# MBusTransmitter.net
KiCad netlist of a schematic drawn in EAGLE
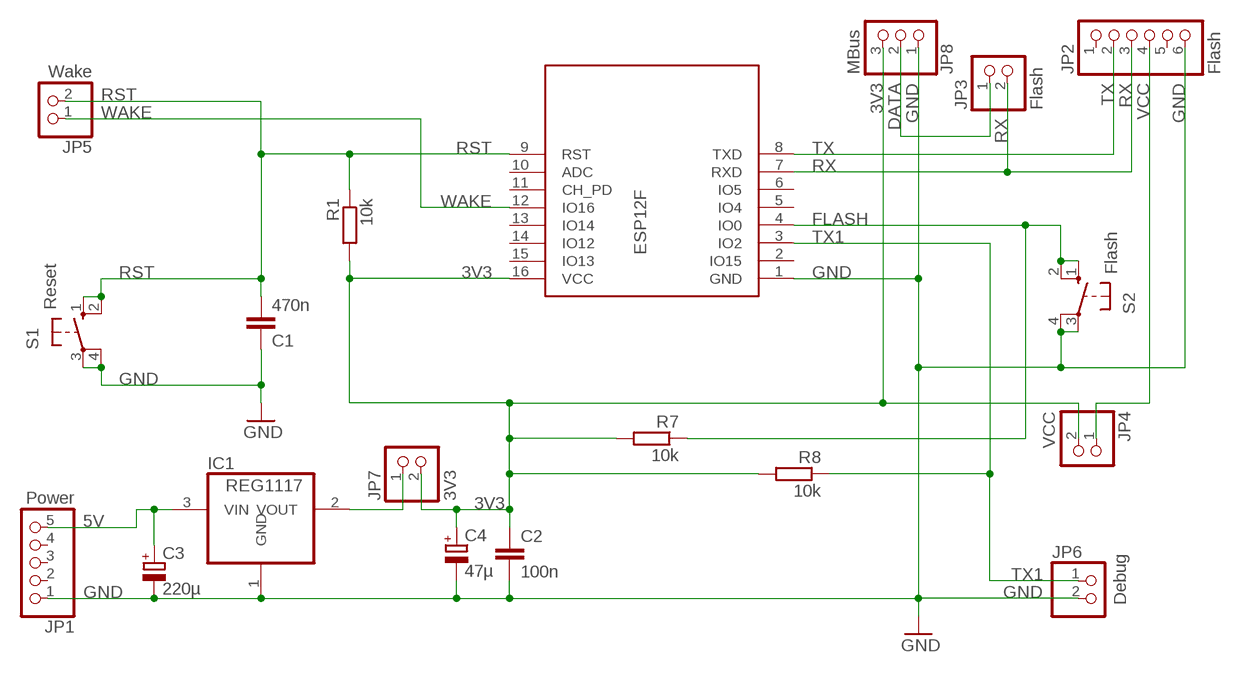
[diagram p0: schematic, sheet 1]

(export (version "E")
  (design (tool "Eeschema 10.0.6"))
  (components
    (comp (ref "C1")
      (value "470n")
      (footprint "eagle-import:C050-024X044")
      (libsource (lib "eagle-import") (part "C-EU050-024X044"))
    )
    (comp (ref "C2")
      (value "100n")
      (footprint "eagle-import:C050-024X044")
      (libsource (lib "eagle-import") (part "C-EU050-024X044"))
    )
    (comp (ref "C3")
      (value "220µ")
      (footprint "eagle-import:E5-10,5")
      (libsource (lib "eagle-import") (part "CPOL-EUE5-10.5"))
    )
    (comp (ref "C4")
      (value "47µ")
      (footprint "eagle-import:E2,5-5")
      (libsource (lib "eagle-import") (part "CPOL-EUE2.5-5"))
    )
    (comp (ref "IC1")
      (value "REG1117")
      (footprint "eagle-import:SOT223")
      (libsource (lib "eagle-import") (part "REG1117"))
    )
    (comp (ref "JP1")
      (value "Power")
      (footprint "eagle-import:1X05")
      (libsource (lib "eagle-import") (part "PINHD-1X5"))
    )
    (comp (ref "JP2")
      (value "Flash")
      (footprint "eagle-import:1X06")
      (libsource (lib "eagle-import") (part "PINHD-1X6"))
    )
    (comp (ref "JP3")
      (value "Flash")
      (footprint "eagle-import:1X02")
      (libsource (lib "eagle-import") (part "PINHD-1X2"))
    )
    (comp (ref "JP4")
      (value "VCC")
      (footprint "eagle-import:1X02")
      (libsource (lib "eagle-import") (part "PINHD-1X2"))
    )
    (comp (ref "JP5")
      (value "Wake")
      (footprint "eagle-import:1X02")
      (libsource (lib "eagle-import") (part "PINHD-1X2"))
    )
    (comp (ref "JP6")
      (value "Debug")
      (footprint "eagle-import:1X02")
      (libsource (lib "eagle-import") (part "PINHD-1X2"))
    )
    (comp (ref "JP7")
      (value "3V3")
      (footprint "eagle-import:1X02")
      (libsource (lib "eagle-import") (part "PINHD-1X2"))
    )
    (comp (ref "JP8")
      (value "MBus")
      (footprint "eagle-import:1X03_90")
      (libsource (lib "eagle-import") (part "PINHD-1X3/90"))
    )
    (comp (ref "R1")
      (value "10k")
      (footprint "eagle-import:0207_10")
      (libsource (lib "eagle-import") (part "R-EU_0207/10"))
    )
    (comp (ref "R7")
      (value "10k")
      (footprint "eagle-import:0207_10")
      (libsource (lib "eagle-import") (part "R-EU_0207/10"))
    )
    (comp (ref "R8")
      (value "10k")
      (footprint "eagle-import:0207_10")
      (libsource (lib "eagle-import") (part "R-EU_0207/10"))
    )
    (comp (ref "S1")
      (value "Reset")
      (footprint "eagle-import:B3F-10XX")
      (fields (field (name "MPN") "B3F-1000"))
      (libsource (lib "eagle-import") (part "10-XX"))
    )
    (comp (ref "S2")
      (value "Flash")
      (footprint "eagle-import:B3F-10XX")
      (fields (field (name "MPN") "B3F-1000"))
      (libsource (lib "eagle-import") (part "10-XX"))
    )
    (comp (ref "U$2")
      (value "ESP12F")
      (footprint "eagle-import:ESP12F")
      (libsource (lib "eagle-import") (part "ESP12F"))
    )
  )
  (nets
    (net (code "1") (name "/3V3") (class "Default")
      (node (ref "C2") (pin "1") (pinfunction "1_1") (pintype "passive"))
      (node (ref "C4") (pin "+") (pinfunction "+_+") (pintype "passive"))
      (node (ref "JP4") (pin "2") (pinfunction "2_2") (pintype "passive"))
      (node (ref "JP7") (pin "2") (pinfunction "2_2") (pintype "passive"))
      (node (ref "JP8") (pin "3") (pinfunction "3_3") (pintype "passive"))
      (node (ref "R1") (pin "2") (pinfunction "2_2") (pintype "passive"))
      (node (ref "R7") (pin "2") (pinfunction "2_2") (pintype "passive"))
      (node (ref "R8") (pin "2") (pinfunction "2_2") (pintype "passive"))
      (node (ref "U$2") (pin "16") (pinfunction "VCC_16") (pintype "bidirectional"))
    )
    (net (code "2") (name "/5V") (class "Default")
      (node (ref "C3") (pin "+") (pinfunction "+_+") (pintype "passive"))
      (node (ref "IC1") (pin "3") (pinfunction "VIN_3") (pintype "input"))
      (node (ref "JP1") (pin "5") (pinfunction "5_5") (pintype "passive"))
    )
    (net (code "3") (name "/DATA") (class "Default")
      (node (ref "JP3") (pin "1") (pinfunction "1_1") (pintype "passive"))
      (node (ref "JP8") (pin "2") (pinfunction "2_2") (pintype "passive"))
    )
    (net (code "4") (name "/FLASH") (class "Default")
      (node (ref "R7") (pin "1") (pinfunction "1_1") (pintype "passive"))
      (node (ref "S2") (pin "1") (pinfunction "S_1") (pintype "passive"))
      (node (ref "S2") (pin "2") (pinfunction "S1_2") (pintype "passive"))
      (node (ref "U$2") (pin "4") (pinfunction "IO0_4") (pintype "bidirectional"))
    )
    (net (code "5") (name "/RST") (class "Default")
      (node (ref "C1") (pin "2") (pinfunction "2_2") (pintype "passive"))
      (node (ref "JP5") (pin "2") (pinfunction "2_2") (pintype "passive"))
      (node (ref "R1") (pin "1") (pinfunction "1_1") (pintype "passive"))
      (node (ref "S1") (pin "1") (pinfunction "S_1") (pintype "passive"))
      (node (ref "S1") (pin "2") (pinfunction "S1_2") (pintype "passive"))
      (node (ref "U$2") (pin "9") (pinfunction "RST_9") (pintype "bidirectional"))
    )
    (net (code "6") (name "/RX") (class "Default")
      (node (ref "JP2") (pin "3") (pinfunction "3_3") (pintype "passive"))
      (node (ref "JP3") (pin "2") (pinfunction "2_2") (pintype "passive"))
      (node (ref "U$2") (pin "7") (pinfunction "RXD_7") (pintype "bidirectional"))
    )
    (net (code "7") (name "/TX") (class "Default")
      (node (ref "JP2") (pin "2") (pinfunction "2_2") (pintype "passive"))
      (node (ref "U$2") (pin "8") (pinfunction "TXD_8") (pintype "bidirectional"))
    )
    (net (code "8") (name "/TX1") (class "Default")
      (node (ref "JP6") (pin "1") (pinfunction "1_1") (pintype "passive"))
      (node (ref "R8") (pin "1") (pinfunction "1_1") (pintype "passive"))
      (node (ref "U$2") (pin "3") (pinfunction "IO2_3") (pintype "bidirectional"))
    )
    (net (code "9") (name "/VCC") (class "Default")
      (node (ref "JP2") (pin "4") (pinfunction "4_4") (pintype "passive"))
      (node (ref "JP4") (pin "1") (pinfunction "1_1") (pintype "passive"))
    )
    (net (code "10") (name "/WAKE") (class "Default")
      (node (ref "JP5") (pin "1") (pinfunction "1_1") (pintype "passive"))
      (node (ref "U$2") (pin "12") (pinfunction "IO16_12") (pintype "bidirectional"))
    )
    (net (code "11") (name "GND") (class "Default")
      (node (ref "C1") (pin "1") (pinfunction "1_1") (pintype "passive"))
      (node (ref "C2") (pin "2") (pinfunction "2_2") (pintype "passive"))
      (node (ref "C3") (pin "-") (pinfunction "-_-") (pintype "passive"))
      (node (ref "C4") (pin "-") (pinfunction "-_-") (pintype "passive"))
      (node (ref "IC1") (pin "1") (pinfunction "GND_1") (pintype "power_in"))
      (node (ref "JP1") (pin "1") (pinfunction "1_1") (pintype "passive"))
      (node (ref "JP2") (pin "6") (pinfunction "6_6") (pintype "passive"))
      (node (ref "JP6") (pin "2") (pinfunction "2_2") (pintype "passive"))
      (node (ref "JP8") (pin "1") (pinfunction "1_1") (pintype "passive"))
      (node (ref "S1") (pin "3") (pinfunction "P_3") (pintype "passive"))
      (node (ref "S1") (pin "4") (pinfunction "P1_4") (pintype "passive"))
      (node (ref "S2") (pin "3") (pinfunction "P_3") (pintype "passive"))
      (node (ref "S2") (pin "4") (pinfunction "P1_4") (pintype "passive"))
      (node (ref "U$2") (pin "1") (pinfunction "GND_1") (pintype "bidirectional"))
    )
    (net (code "12") (name "Net-(IC1-VOUT)") (class "Default")
      (node (ref "IC1") (pin "2") (pinfunction "VOUT_2") (pintype "output"))
      (node (ref "JP7") (pin "1") (pinfunction "1_1") (pintype "passive"))
    )
    (net (code "13") (name "unconnected-(JP1-Pad2)") (class "Default")
      (node (ref "JP1") (pin "2") (pinfunction "2_2") (pintype "passive"))
    )
    (net (code "14") (name "unconnected-(JP1-Pad3)") (class "Default")
      (node (ref "JP1") (pin "3") (pinfunction "3_3") (pintype "passive"))
    )
    (net (code "15") (name "unconnected-(JP1-Pad4)") (class "Default")
      (node (ref "JP1") (pin "4") (pinfunction "4_4") (pintype "passive"))
    )
    (net (code "16") (name "unconnected-(JP2-Pad1)") (class "Default")
      (node (ref "JP2") (pin "1") (pinfunction "1_1") (pintype "passive"))
    )
    (net (code "17") (name "unconnected-(JP2-Pad5)") (class "Default")
      (node (ref "JP2") (pin "5") (pinfunction "5_5") (pintype "passive"))
    )
    (net (code "18") (name "unconnected-(U$2-ADC-Pad10)") (class "Default")
      (node (ref "U$2") (pin "10") (pinfunction "ADC_10") (pintype "bidirectional"))
    )
    (net (code "19") (name "unconnected-(U$2-CH_PD-Pad11)") (class "Default")
      (node (ref "U$2") (pin "11") (pinfunction "CH_PD_11") (pintype "bidirectional"))
    )
    (net (code "20") (name "unconnected-(U$2-IO4-Pad5)") (class "Default")
      (node (ref "U$2") (pin "5") (pinfunction "IO4_5") (pintype "bidirectional"))
    )
    (net (code "21") (name "unconnected-(U$2-IO5-Pad6)") (class "Default")
      (node (ref "U$2") (pin "6") (pinfunction "IO5_6") (pintype "bidirectional"))
    )
    (net (code "22") (name "unconnected-(U$2-IO12-Pad14)") (class "Default")
      (node (ref "U$2") (pin "14") (pinfunction "IO12_14") (pintype "bidirectional"))
    )
    (net (code "23") (name "unconnected-(U$2-IO13-Pad15)") (class "Default")
      (node (ref "U$2") (pin "15") (pinfunction "IO13_15") (pintype "bidirectional"))
    )
    (net (code "24") (name "unconnected-(U$2-IO14-Pad13)") (class "Default")
      (node (ref "U$2") (pin "13") (pinfunction "IO14_13") (pintype "bidirectional"))
    )
    (net (code "25") (name "unconnected-(U$2-IO15-Pad2)") (class "Default")
      (node (ref "U$2") (pin "2") (pinfunction "IO15_2") (pintype "bidirectional"))
    )
  )
)
